# LTC3560-3_3-800mA.net
KiCad netlist of a schematic drawn in Altium Designer
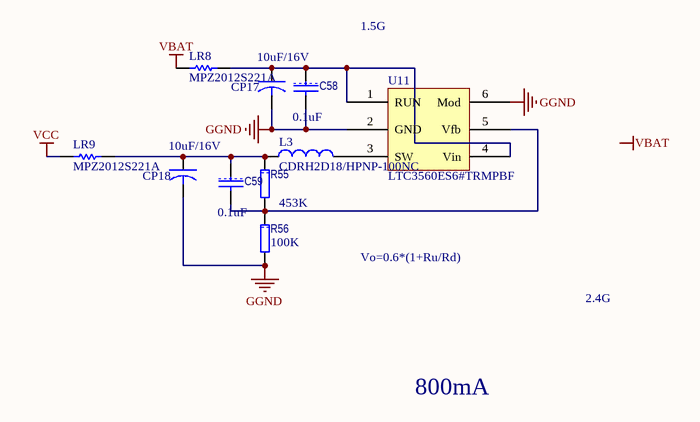
[diagram p0: LTC3560-3.3-800mA_电源.SchDoc]

(export (version "E")
  (design (tool "Eeschema 10.0.6"))
  (components
    (comp (ref "C58")
      (value "0.1uF")
      (footprint "1608[0603]C")
      (description "多层陶瓷电容器MLCC - SMD/SMT 0603 0.1uF 50volts X7R 10%")
      (fields (field (name "MANUFACTURER") "TDK") (field (name "MANUFACTURER PART NUMBER") "C1608X7R1H104K"))
      (libsource (lib "*") (part "CAP"))
    )
    (comp (ref "C59")
      (value "0.1uF")
      (footprint "1608[0603]C")
      (description "多层陶瓷电容器MLCC - SMD/SMT 0603 0.1uF 50volts X7R 10%")
      (fields (field (name "MANUFACTURER") "TDK") (field (name "MANUFACTURER PART NUMBER") "C1608X7R1H104K"))
      (libsource (lib "*") (part "CAP"))
    )
    (comp (ref "CP17")
      (value "10uF/16V")
      (footprint "3216[1206]CB")
      (description "钽质电容器-固体SMD 16volts 10uF 10%")
      (fields (field (name "MANUFACTURER") "AVX") (field (name "MANUFACTURER PART NUMBER") "TAJA106K016RNJ"))
      (libsource (lib "*") (part "CAPACITOR"))
    )
    (comp (ref "CP18")
      (value "10uF/16V")
      (footprint "3216[1206]CB")
      (description "钽质电容器-固体SMD 16volts 10uF 10%")
      (fields (field (name "MANUFACTURER") "AVX") (field (name "MANUFACTURER PART NUMBER") "TAJA106K016RNJ"))
      (libsource (lib "*") (part "CAPACITOR"))
    )
    (comp (ref "L3")
      (value "CDRH2D18/HPNP-100NC")
      (footprint "INDP3232")
      (description "固定电感器 10uH 430mA")
      (fields (field (name "MANUFACTURER") "Sumida"))
      (libsource (lib "Miscellaneous Devices") (part "Inductor"))
    )
    (comp (ref "LR8")
      (value "MPZ2012S221A")
      (footprint "2012[0805]")
      (description "电磁干扰滤波珠子、扼流圈和阵列 Ferrite Chip Beads")
      (fields (field (name "MANUFACTURER") "TDK"))
      (libsource (lib "Miscellaneous Devices") (part "Res Semi"))
    )
    (comp (ref "LR9")
      (value "MPZ2012S221A")
      (footprint "2012[0805]")
      (description "电磁干扰滤波珠子、扼流圈和阵列 Ferrite Chip Beads")
      (fields (field (name "MANUFACTURER") "TDK"))
      (libsource (lib "Miscellaneous Devices") (part "Res Semi"))
    )
    (comp (ref "R55")
      (value "453K")
      (footprint "1608[0603]R")
      (description "薄膜电阻器 - SMD 453Kohms .1% 25ppm")
      (fields
        (field (name "MANUFACTURER") "Vishay")
        (field (name "MANUFACTURER PART NUMBER") "TNPW0805453KBEEN")
      )
      (libsource (lib "10K 1%") (part "RES"))
    )
    (comp (ref "R56")
      (value "100K")
      (footprint "1608[0603]R")
      (description "厚膜电阻器 - SMD 1/10watt 100Kohms 1%")
      (fields
        (field (name "MANUFACTURER") "Vishay / Dale")
        (field (name "MANUFACTURER PART NUMBER") "CRCW0603100KFKEA")
      )
      (libsource (lib "100K 1%") (part "RES"))
    )
    (comp (ref "U11")
      (value "LTC3560ES6#TRMPBF")
      (footprint "SOT26A-6N")
      (description "IC REG BUCK SYNC ADJ TSOT23-6")
      (fields (field (name "MANUFACTURER") "Linear Technology"))
      (libsource (lib "S3C2440V9") (part "LTC3405A"))
    )
  )
  (nets
    (net (code "1") (name "GGND") (class "Default")
      (node (ref "C58") (pin "2") (pinfunction "2_2") (pintype "passive"))
      (node (ref "CP17") (pin "2") (pinfunction "2_2") (pintype "passive"))
      (node (ref "CP18") (pin "2") (pinfunction "2_2") (pintype "passive"))
      (node (ref "R56") (pin "2") (pinfunction "2_2") (pintype "passive"))
      (node (ref "U11") (pin "2") (pinfunction "GND_2") (pintype "passive"))
      (node (ref "U11") (pin "6") (pinfunction "Mod_6") (pintype "passive"))
    )
    (net (code "2") (name "Net-(C59-Pad1)") (class "Default")
      (node (ref "C59") (pin "1") (pinfunction "1_1") (pintype "passive"))
      (node (ref "CP18") (pin "1") (pinfunction "1_1") (pintype "passive"))
      (node (ref "L3") (pin "1") (pinfunction "1_1") (pintype "passive"))
      (node (ref "LR9") (pin "1") (pinfunction "1_1") (pintype "passive"))
      (node (ref "R55") (pin "1") (pinfunction "1_1") (pintype "passive"))
    )
    (net (code "3") (name "Net-(U11-RUN)") (class "Default")
      (node (ref "C58") (pin "1") (pinfunction "1_1") (pintype "passive"))
      (node (ref "CP17") (pin "1") (pinfunction "1_1") (pintype "passive"))
      (node (ref "LR8") (pin "1") (pinfunction "1_1") (pintype "passive"))
      (node (ref "U11") (pin "1") (pinfunction "RUN_1") (pintype "passive"))
      (node (ref "U11") (pin "4") (pinfunction "Vin_4") (pintype "passive"))
    )
    (net (code "4") (name "Net-(U11-SW)") (class "Default")
      (node (ref "L3") (pin "2") (pinfunction "2_2") (pintype "passive"))
      (node (ref "U11") (pin "3") (pinfunction "SW_3") (pintype "passive"))
    )
    (net (code "5") (name "Net-(U11-Vfb)") (class "Default")
      (node (ref "C59") (pin "2") (pinfunction "2_2") (pintype "passive"))
      (node (ref "R55") (pin "2") (pinfunction "2_2") (pintype "passive"))
      (node (ref "R56") (pin "1") (pinfunction "1_1") (pintype "passive"))
      (node (ref "U11") (pin "5") (pinfunction "Vfb_5") (pintype "passive"))
    )
    (net (code "6") (name "VBAT") (class "Default")
      (node (ref "LR8") (pin "2") (pinfunction "2_2") (pintype "passive"))
    )
    (net (code "7") (name "VCC") (class "Default")
      (node (ref "LR9") (pin "2") (pinfunction "2_2") (pintype "passive"))
    )
  )
)
